# WIFI.net
KiCad netlist of a schematic drawn in Altium Designer
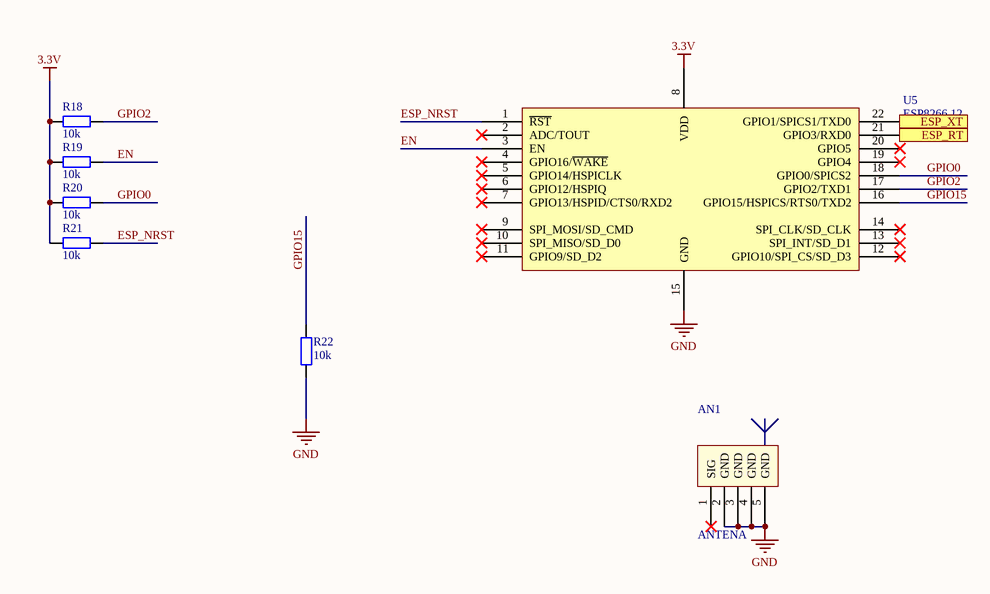
[diagram p0: WIFI.SchDoc]

(export (version "E")
  (design (tool "Eeschema 10.0.6"))
  (components
    (comp (ref "AN1")
      (value "ANTENA")
      (footprint "DE ANTEN SMA CONG")
      (description "Generic Antenna")
      (libsource (lib "Altium_Lib_by_KhueNguyenCreator") (part "ANTEN SMA CONG"))
    )
    (comp (ref "R18")
      (value "10k")
      (footprint "tro smd 0603")
      (description "Dán")
      (libsource (lib "Altium_Lib_by_KhueNguyenCreator") (part "Tro 0603 5% 10k"))
    )
    (comp (ref "R19")
      (value "10k")
      (footprint "tro smd 0603")
      (description "Dán")
      (libsource (lib "Altium_Lib_by_KhueNguyenCreator") (part "Tro 0603 5% 10k"))
    )
    (comp (ref "R20")
      (value "10k")
      (footprint "tro smd 0603")
      (description "Dán")
      (libsource (lib "Altium_Lib_by_KhueNguyenCreator") (part "Tro 0603 5% 10k"))
    )
    (comp (ref "R21")
      (value "10k")
      (footprint "tro smd 0603")
      (description "Dán")
      (libsource (lib "Altium_Lib_by_KhueNguyenCreator") (part "Tro 0603 5% 10k"))
    )
    (comp (ref "R22")
      (value "10k")
      (footprint "tro smd 0603")
      (description "Dán")
      (libsource (lib "Altium_Lib_by_KhueNguyenCreator") (part "Tro 0603 5% 10k"))
    )
    (comp (ref "U5")
      (value "ESP8266 12")
      (footprint "ESP8266 12")
      (description "ESP8266 12 22 Pin")
      (libsource (lib "Altium_Lib_by_KhueNguyenCreator") (part "ESP8266 12"))
    )
  )
  (nets
    (net (code "1") (name "/EN") (class "Default")
      (node (ref "R19") (pin "2") (pinfunction "2_2") (pintype "passive"))
      (node (ref "U5") (pin "3") (pinfunction "EN_3") (pintype "passive"))
    )
    (net (code "2") (name "/ESP_NRST") (class "Default")
      (node (ref "R21") (pin "2") (pinfunction "2_2") (pintype "passive"))
      (node (ref "U5") (pin "1") (pinfunction "~{RST}_1") (pintype "passive"))
    )
    (net (code "3") (name "/ESP_RT") (class "Default")
      (node (ref "U5") (pin "21") (pinfunction "GPIO3/RXD0_21") (pintype "passive"))
    )
    (net (code "4") (name "/ESP_XT") (class "Default")
      (node (ref "U5") (pin "22") (pinfunction "GPIO1/SPICS1/TXD0_22") (pintype "passive"))
    )
    (net (code "5") (name "/GPIO0") (class "Default")
      (node (ref "R20") (pin "2") (pinfunction "2_2") (pintype "passive"))
      (node (ref "U5") (pin "18") (pinfunction "GPIO0/SPICS2_18") (pintype "passive"))
    )
    (net (code "6") (name "/GPIO2") (class "Default")
      (node (ref "R18") (pin "2") (pinfunction "2_2") (pintype "passive"))
      (node (ref "U5") (pin "17") (pinfunction "GPIO2/TXD1_17") (pintype "passive"))
    )
    (net (code "7") (name "/GPIO15") (class "Default")
      (node (ref "R22") (pin "2") (pinfunction "2_2") (pintype "passive"))
      (node (ref "U5") (pin "16") (pinfunction "GPIO15/HSPICS/RTS0/TXD2_16") (pintype "passive"))
    )
    (net (code "8") (name "3.3V") (class "Default")
      (node (ref "R18") (pin "1") (pinfunction "1_1") (pintype "passive"))
      (node (ref "R19") (pin "1") (pinfunction "1_1") (pintype "passive"))
      (node (ref "R20") (pin "1") (pinfunction "1_1") (pintype "passive"))
      (node (ref "R21") (pin "1") (pinfunction "1_1") (pintype "passive"))
      (node (ref "U5") (pin "8") (pinfunction "VDD_8") (pintype "passive"))
    )
    (net (code "9") (name "GND") (class "Default")
      (node (ref "AN1") (pin "2") (pinfunction "GND_2") (pintype "passive"))
      (node (ref "AN1") (pin "3") (pinfunction "GND_3") (pintype "passive"))
      (node (ref "AN1") (pin "4") (pinfunction "GND_4") (pintype "passive"))
      (node (ref "AN1") (pin "5") (pinfunction "GND_5") (pintype "passive"))
      (node (ref "R22") (pin "1") (pinfunction "1_1") (pintype "passive"))
      (node (ref "U5") (pin "15") (pinfunction "GND_15") (pintype "passive"))
    )
    (net (code "10") (name "unconnected-(AN1-SIG-Pad1)") (class "Default")
      (node (ref "AN1") (pin "1") (pinfunction "SIG_1") (pintype "passive+no_connect"))
    )
    (net (code "11") (name "unconnected-(U5-ADC{slash}TOUT-Pad2)") (class "Default")
      (node (ref "U5") (pin "2") (pinfunction "ADC/TOUT_2") (pintype "passive+no_connect"))
    )
    (net (code "12") (name "unconnected-(U5-GPIO4-Pad19)") (class "Default")
      (node (ref "U5") (pin "19") (pinfunction "GPIO4_19") (pintype "passive+no_connect"))
    )
    (net (code "13") (name "unconnected-(U5-GPIO5-Pad20)") (class "Default")
      (node (ref "U5") (pin "20") (pinfunction "GPIO5_20") (pintype "passive+no_connect"))
    )
    (net (code "14") (name "unconnected-(U5-GPIO9{slash}SD_D2-Pad11)") (class "Default")
      (node (ref "U5") (pin "11") (pinfunction "GPIO9/SD_D2_11") (pintype "passive+no_connect"))
    )
    (net (code "15") (name "unconnected-(U5-GPIO10{slash}SPI_CS{slash}SD_D3-Pad12)") (class "Default")
      (node (ref "U5") (pin "12") (pinfunction "GPIO10/SPI_CS/SD_D3_12") (pintype "passive+no_connect"))
    )
    (net (code "16") (name "unconnected-(U5-GPIO12{slash}HSPIQ-Pad6)") (class "Default")
      (node (ref "U5") (pin "6") (pinfunction "GPIO12/HSPIQ_6") (pintype "passive+no_connect"))
    )
    (net (code "17") (name "unconnected-(U5-GPIO13{slash}HSPID{slash}CTS0{slash}RXD2-Pad7)") (class "Default")
      (node (ref "U5") (pin "7") (pinfunction "GPIO13/HSPID/CTS0/RXD2_7") (pintype "passive+no_connect"))
    )
    (net (code "18") (name "unconnected-(U5-GPIO14{slash}HSPICLK-Pad5)") (class "Default")
      (node (ref "U5") (pin "5") (pinfunction "GPIO14/HSPICLK_5") (pintype "passive+no_connect"))
    )
    (net (code "19") (name "unconnected-(U5-GPIO16{slash}~{WAKE}-Pad4)") (class "Default")
      (node (ref "U5") (pin "4") (pinfunction "GPIO16/~{WAKE}_4") (pintype "passive+no_connect"))
    )
    (net (code "20") (name "unconnected-(U5-SPI_CLK{slash}SD_CLK-Pad14)") (class "Default")
      (node (ref "U5") (pin "14") (pinfunction "SPI_CLK/SD_CLK_14") (pintype "passive+no_connect"))
    )
    (net (code "21") (name "unconnected-(U5-SPI_INT{slash}SD_D1-Pad13)") (class "Default")
      (node (ref "U5") (pin "13") (pinfunction "SPI_INT/SD_D1_13") (pintype "passive+no_connect"))
    )
    (net (code "22") (name "unconnected-(U5-SPI_MISO{slash}SD_D0-Pad10)") (class "Default")
      (node (ref "U5") (pin "10") (pinfunction "SPI_MISO/SD_D0_10") (pintype "passive+no_connect"))
    )
    (net (code "23") (name "unconnected-(U5-SPI_MOSI{slash}SD_CMD-Pad9)") (class "Default")
      (node (ref "U5") (pin "9") (pinfunction "SPI_MOSI/SD_CMD_9") (pintype "passive+no_connect"))
    )
  )
)
